# 110_ESP32s3.net
KiCad netlist of a schematic drawn in Altium Designer
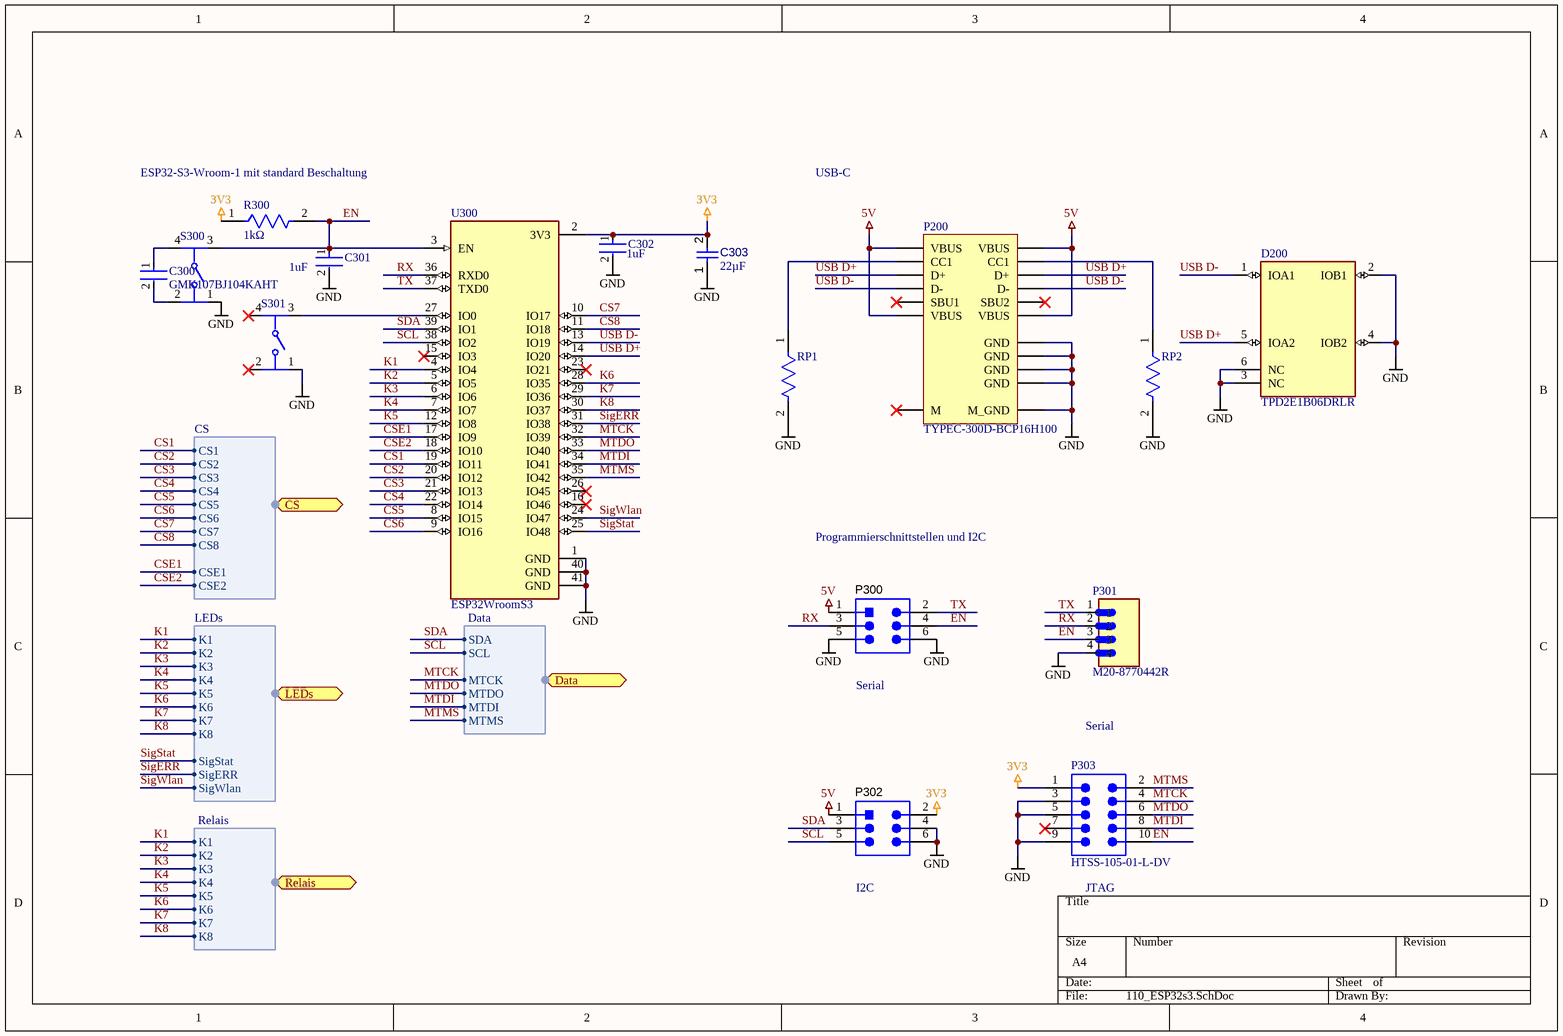
[diagram p0: 110_ESP32s3.SchDoc]

(export (version "E")
  (design (tool "Eeschema 10.0.6"))
  (components
    (comp (ref "C300")
      (value "GMK107BJ104KAHT")
      (footprint "FP-0603-L_1_6_0_1-W_0_8_0-IPC_B")
      (description "Ceramic Capacitor Automotive 0.1uF ±10% 35V X5R 0603")
      (fields (field (name "TOLERANCE") "10%"))
      (libsource (lib "Altium Content Vault") (part "02cd4be3c70576c341d710602a673aa"))
    )
    (comp (ref "C301")
      (value "1uF")
      (footprint "FP-CGA3E-0_3-0_1-MFG")
      (description "Cap Ceramic 1uF 35V X7R 10% Pad SMD 0603 +125°C Automotive T/R\r\nCGA3E1X7R1V105K080AC")
      (fields (field (name "TOLERANCE") "10%"))
      (libsource (lib "Altium Content Vault") (part "b4654b650e69147ec39a6b967a45e02"))
    )
    (comp (ref "C302")
      (value "1uF")
      (footprint "FP-CGA3E-0_3-0_1-MFG")
      (description "Cap Ceramic 1uF 35V X7R 10% Pad SMD 0603 +125°C Automotive T/R\r\nCGA3E1X7R1V105K080AC")
      (fields (field (name "TOLERANCE") "10%"))
      (libsource (lib "Altium Content Vault") (part "b4654b650e69147ec39a6b967a45e02"))
    )
    (comp (ref "C303")
      (value "22µF")
      (footprint "CAPC0805(2012)145_L")
      (description "Chip Capacitor, 22µF +/-40%, 16V, 0805, Thickness 1.45 mm")
      (fields (field (name "TOLERANCE") "5%") (field (name "Comment") "Capacitor 22µF +/-40% 16V 0805"))
      (libsource (lib "Milutin") (part "CAP-NP-2"))
    )
    (comp (ref "D200")
      (value "TPD2E1B06DRLR")
      (footprint "FP-DRL0006A-MFG")
      (description "TVS DIODE 5.5V 15V 6SOT")
      (fields
        (field (name "OCTOPART") "https://octopart.com/tpd2e1b06drlr-texas+instruments-30488860")
        (field (name "MANUFACTURER") "Texas Instruments")
      )
      (libsource (lib "Altium Content Vault") (part "f3dc085ebb28d99bc65c213f373c040"))
    )
    (comp (ref "P200")
      (value "TYPEC-300D-BCP16H100")
      (footprint "TYPEC-300D-BCP16H100-Footprint-1")
      (description "Vertical USB Type C Connector")
      (libsource (lib "Milutin") (part "TYPEC-300D-BCP16H100-Symbol-1"))
    )
    (comp (ref "P300")
      (value "5-146130-2")
      (footprint "TECO-5-146130-2_V")
      (description "Male Header, Pitch 2.54 mm, 2 x 3 Position, Height 8.13 mm, -65 to 125 degC, RoHS, Tube")
      (libsource (lib "Altium Content Vault") (part "CN-2P-M-R6"))
    )
    (comp (ref "P301")
      (value "M20-8770442R")
      (footprint "HARWIN_M20-8770442R")
      (description "Connector Header Surface Mount 4 position 0.100 (2.54mm)")
      (fields (field (name "MF") "Harwin Inc."))
      (libsource (lib "AltiumLib_MILUTIN") (part "M20-8770442R"))
    )
    (comp (ref "P302")
      (value "5-146130-2")
      (footprint "TECO-5-146130-2_V")
      (description "Male Header, Pitch 2.54 mm, 2 x 3 Position, Height 8.13 mm, -65 to 125 degC, RoHS, Tube")
      (libsource (lib "Altium Content Vault") (part "CN-2P-M-R6"))
    )
    (comp (ref "P303")
      (value "HTSS-105-01-L-DV")
      (footprint "SMTC-HTSS-105-01-X-DV")
      (fields (field (name "MANUFACTURER") "Samtec"))
      (libsource (lib "Altium Content Vault") (part "SMTC-HTSS-105-01-X-DV"))
    )
    (comp (ref "R300")
      (value "1kΩ")
      (footprint "FP-CRCW0603-e3-MFG")
      (description "RES Thick Film, 1kΩ, 1%, 0.1W, 100ppm/°C, 0603, CRCW06031K00FKEA")
      (fields (field (name "TOLERANCE") "1%"))
      (libsource (lib "Altium Content Vault") (part "1029c3af85768c4190bb7ad29bc67b5"))
    )
    (comp (ref "RP1")
      (value "CRCW06035K10FKEA")
      (footprint "FP-CRCW0603-e3-IPC_C")
      (description "RES Thick Film, 5.1kΩ, 1%, 0.1W, 100ppm/°C, 0603")
      (fields (field (name "TOLERANCE") "1%"))
      (libsource (lib "Altium Content Vault") (part "1029c3af85768c4190bb7ad29bc67b5"))
    )
    (comp (ref "RP2")
      (value "CRCW06035K10FKEA")
      (footprint "FP-CRCW0603-e3-IPC_C")
      (description "RES Thick Film, 5.1kΩ, 1%, 0.1W, 100ppm/°C, 0603")
      (fields (field (name "TOLERANCE") "1%"))
      (libsource (lib "Altium Content Vault") (part "1029c3af85768c4190bb7ad29bc67b5"))
    )
    (comp (ref "S300")
      (value "~")
      (footprint "FP-PTS645SM43SMTR92LFS-MFG")
      (description "SWITCH TACTILE SPST-NO 0.05A 12V\r\nPTS645SM43SMTR92LFS")
      (libsource (lib "Altium Content Vault") (part "1adf0dd01260c80cf25a44bfd6b99ba"))
    )
    (comp (ref "S301")
      (value "~")
      (footprint "FP-PTS645SM43SMTR92LFS-MFG")
      (description "SWITCH TACTILE SPST-NO 0.05A 12V\r\nPTS645SM43SMTR92LFS")
      (libsource (lib "Altium Content Vault") (part "1adf0dd01260c80cf25a44bfd6b99ba"))
    )
    (comp (ref "U300")
      (value "ESP32WroomS3")
      (footprint "ESP32WroomS3")
      (fields (field (name "SOURCE") "Schaltdose.SchLib"))
      (libsource (lib "Milutin") (part "ESP32WroomS3"))
    )
  )
  (nets
    (net (code "5") (name "/CS1") (class "Default")
      (node (ref "U300") (pin "19") (pinfunction "IO11_19") (pintype "bidirectional"))
    )
    (net (code "6") (name "/CS2") (class "Default")
      (node (ref "U300") (pin "20") (pinfunction "IO12_20") (pintype "bidirectional"))
    )
    (net (code "7") (name "/CS3") (class "Default")
      (node (ref "U300") (pin "21") (pinfunction "IO13_21") (pintype "bidirectional"))
    )
    (net (code "8") (name "/CS4") (class "Default")
      (node (ref "U300") (pin "22") (pinfunction "IO14_22") (pintype "bidirectional"))
    )
    (net (code "9") (name "/CS5") (class "Default")
      (node (ref "U300") (pin "8") (pinfunction "IO15_8") (pintype "bidirectional"))
    )
    (net (code "10") (name "/CS6") (class "Default")
      (node (ref "U300") (pin "9") (pinfunction "IO16_9") (pintype "bidirectional"))
    )
    (net (code "11") (name "/CS7") (class "Default")
      (node (ref "U300") (pin "10") (pinfunction "IO17_10") (pintype "bidirectional"))
    )
    (net (code "12") (name "/CS8") (class "Default")
      (node (ref "U300") (pin "11") (pinfunction "IO18_11") (pintype "bidirectional"))
    )
    (net (code "13") (name "/CSE1") (class "Default")
      (node (ref "U300") (pin "17") (pinfunction "IO9_17") (pintype "bidirectional"))
    )
    (net (code "14") (name "/CSE2") (class "Default")
      (node (ref "U300") (pin "18") (pinfunction "IO10_18") (pintype "bidirectional"))
    )
    (net (code "15") (name "/EN") (class "Default")
      (node (ref "C301") (pin "1") (pinfunction "1_1") (pintype "passive"))
      (node (ref "P300") (pin "4") (pinfunction "4_4") (pintype "passive"))
      (node (ref "P301") (pin "3") (pinfunction "3_3") (pintype "passive"))
      (node (ref "P303") (pin "10") (pinfunction "10_10") (pintype "passive"))
      (node (ref "R300") (pin "2") (pinfunction "2_2") (pintype "passive"))
      (node (ref "S300") (pin "3") (pinfunction "3_3") (pintype "passive"))
      (node (ref "U300") (pin "3") (pinfunction "EN_3") (pintype "input"))
    )
    (net (code "16") (name "/K1") (class "Default")
      (node (ref "U300") (pin "4") (pinfunction "IO4_4") (pintype "bidirectional"))
    )
    (net (code "17") (name "/K2") (class "Default")
      (node (ref "U300") (pin "5") (pinfunction "IO5_5") (pintype "bidirectional"))
    )
    (net (code "18") (name "/K3") (class "Default")
      (node (ref "U300") (pin "6") (pinfunction "IO6_6") (pintype "bidirectional"))
    )
    (net (code "19") (name "/K4") (class "Default")
      (node (ref "U300") (pin "7") (pinfunction "IO7_7") (pintype "bidirectional"))
    )
    (net (code "20") (name "/K5") (class "Default")
      (node (ref "U300") (pin "12") (pinfunction "IO8_12") (pintype "bidirectional"))
    )
    (net (code "21") (name "/K6") (class "Default")
      (node (ref "U300") (pin "28") (pinfunction "IO35_28") (pintype "bidirectional"))
    )
    (net (code "22") (name "/K7") (class "Default")
      (node (ref "U300") (pin "29") (pinfunction "IO36_29") (pintype "bidirectional"))
    )
    (net (code "23") (name "/K8") (class "Default")
      (node (ref "U300") (pin "30") (pinfunction "IO37_30") (pintype "bidirectional"))
    )
    (net (code "24") (name "/MTCK") (class "Default")
      (node (ref "P303") (pin "4") (pinfunction "4_4") (pintype "passive"))
      (node (ref "U300") (pin "32") (pinfunction "IO39_32") (pintype "bidirectional"))
    )
    (net (code "25") (name "/MTDI") (class "Default")
      (node (ref "P303") (pin "8") (pinfunction "8_8") (pintype "passive"))
      (node (ref "U300") (pin "34") (pinfunction "IO41_34") (pintype "bidirectional"))
    )
    (net (code "26") (name "/MTDO") (class "Default")
      (node (ref "P303") (pin "6") (pinfunction "6_6") (pintype "passive"))
      (node (ref "U300") (pin "33") (pinfunction "IO40_33") (pintype "bidirectional"))
    )
    (net (code "27") (name "/MTMS") (class "Default")
      (node (ref "P303") (pin "2") (pinfunction "2_2") (pintype "passive"))
      (node (ref "U300") (pin "35") (pinfunction "IO42_35") (pintype "bidirectional"))
    )
    (net (code "28") (name "/RX") (class "Default")
      (node (ref "P300") (pin "3") (pinfunction "3_3") (pintype "passive"))
      (node (ref "P301") (pin "2") (pinfunction "2_2") (pintype "passive"))
      (node (ref "U300") (pin "36") (pinfunction "RXD0_36") (pintype "bidirectional"))
    )
    (net (code "29") (name "/SCL") (class "Default")
      (node (ref "P302") (pin "5") (pinfunction "5_5") (pintype "passive"))
      (node (ref "U300") (pin "38") (pinfunction "IO2_38") (pintype "bidirectional"))
    )
    (net (code "30") (name "/SDA") (class "Default")
      (node (ref "P302") (pin "3") (pinfunction "3_3") (pintype "passive"))
      (node (ref "U300") (pin "39") (pinfunction "IO1_39") (pintype "bidirectional"))
    )
    (net (code "31") (name "/SigERR") (class "Default")
      (node (ref "U300") (pin "31") (pinfunction "IO38_31") (pintype "bidirectional"))
    )
    (net (code "32") (name "/SigStat") (class "Default")
      (node (ref "U300") (pin "25") (pinfunction "IO48_25") (pintype "bidirectional"))
    )
    (net (code "33") (name "/SigWlan") (class "Default")
      (node (ref "U300") (pin "24") (pinfunction "IO47_24") (pintype "bidirectional"))
    )
    (net (code "34") (name "/TX") (class "Default")
      (node (ref "P300") (pin "2") (pinfunction "2_2") (pintype "passive"))
      (node (ref "P301") (pin "1") (pinfunction "1_1") (pintype "passive"))
      (node (ref "U300") (pin "37") (pinfunction "TXD0_37") (pintype "bidirectional"))
    )
    (net (code "35") (name "/USB D+") (class "Default")
      (node (ref "D200") (pin "5") (pinfunction "IOA2_5") (pintype "bidirectional"))
      (node (ref "P200") (pin "A6") (pinfunction "D+_A6") (pintype "passive"))
      (node (ref "P200") (pin "B6") (pinfunction "D+_B6") (pintype "passive"))
      (node (ref "U300") (pin "14") (pinfunction "IO20_14") (pintype "bidirectional"))
    )
    (net (code "36") (name "/USB D-") (class "Default")
      (node (ref "D200") (pin "1") (pinfunction "IOA1_1") (pintype "bidirectional"))
      (node (ref "P200") (pin "A7") (pinfunction "D-_A7") (pintype "passive"))
      (node (ref "P200") (pin "B7") (pinfunction "D-_B7") (pintype "passive"))
      (node (ref "U300") (pin "13") (pinfunction "IO19_13") (pintype "bidirectional"))
    )
    (net (code "41") (name "3V3") (class "Default")
      (node (ref "C302") (pin "1") (pinfunction "1_1") (pintype "passive"))
      (node (ref "C303") (pin "2") (pinfunction "2_2") (pintype "passive"))
      (node (ref "P302") (pin "2") (pinfunction "2_2") (pintype "passive"))
      (node (ref "P303") (pin "1") (pinfunction "1_1") (pintype "passive"))
      (node (ref "R300") (pin "1") (pinfunction "1_1") (pintype "passive"))
      (node (ref "U300") (pin "2") (pinfunction "3V3_2") (pintype "power_in"))
    )
    (net (code "42") (name "5V") (class "Default")
      (node (ref "P200") (pin "A4") (pinfunction "VBUS_A4") (pintype "passive"))
      (node (ref "P200") (pin "A9") (pinfunction "VBUS_A9") (pintype "passive"))
      (node (ref "P200") (pin "B4") (pinfunction "VBUS_B4") (pintype "passive"))
      (node (ref "P200") (pin "B9") (pinfunction "VBUS_B9") (pintype "passive"))
      (node (ref "P300") (pin "1") (pinfunction "1_1") (pintype "passive"))
      (node (ref "P302") (pin "1") (pinfunction "1_1") (pintype "passive"))
    )
    (net (code "43") (name "GND") (class "Default")
      (node (ref "C301") (pin "2") (pinfunction "2_2") (pintype "passive"))
      (node (ref "C302") (pin "2") (pinfunction "2_2") (pintype "passive"))
      (node (ref "C303") (pin "1") (pinfunction "1_1") (pintype "passive"))
      (node (ref "D200") (pin "2") (pinfunction "IOB1_2") (pintype "bidirectional"))
      (node (ref "D200") (pin "3") (pinfunction "NC_3") (pintype "passive"))
      (node (ref "D200") (pin "4") (pinfunction "IOB2_4") (pintype "bidirectional"))
      (node (ref "D200") (pin "6") (pinfunction "NC_6") (pintype "passive"))
      (node (ref "P200") (pin "A1") (pinfunction "GND_A1") (pintype "passive"))
      (node (ref "P200") (pin "A12") (pinfunction "GND_A12") (pintype "passive"))
      (node (ref "P200") (pin "B1") (pinfunction "GND_B1") (pintype "passive"))
      (node (ref "P200") (pin "B12") (pinfunction "GND_B12") (pintype "passive"))
      (node (ref "P200") (pin "M_GND") (pinfunction "M_GND_M_GND") (pintype "passive"))
      (node (ref "P300") (pin "5") (pinfunction "5_5") (pintype "passive"))
      (node (ref "P300") (pin "6") (pinfunction "6_6") (pintype "passive"))
      (node (ref "P301") (pin "4") (pinfunction "4_4") (pintype "passive"))
      (node (ref "P302") (pin "4") (pinfunction "4_4") (pintype "passive"))
      (node (ref "P302") (pin "6") (pinfunction "6_6") (pintype "passive"))
      (node (ref "P303") (pin "3") (pinfunction "3_3") (pintype "passive"))
      (node (ref "P303") (pin "5") (pinfunction "5_5") (pintype "passive"))
      (node (ref "P303") (pin "9") (pinfunction "9_9") (pintype "passive"))
      (node (ref "RP1") (pin "2") (pinfunction "2_2") (pintype "passive"))
      (node (ref "RP2") (pin "2") (pinfunction "2_2") (pintype "passive"))
      (node (ref "S300") (pin "1") (pinfunction "1_1") (pintype "passive"))
      (node (ref "S301") (pin "1") (pinfunction "1_1") (pintype "passive"))
      (node (ref "U300") (pin "1") (pinfunction "GND_1") (pintype "power_in"))
      (node (ref "U300") (pin "40") (pinfunction "GND_40") (pintype "power_in"))
      (node (ref "U300") (pin "41") (pinfunction "GND_41") (pintype "power_in"))
    )
    (net (code "44") (name "Net-(C300-Pad1)") (class "Default")
      (node (ref "C300") (pin "1") (pinfunction "1_1") (pintype "passive"))
      (node (ref "S300") (pin "4") (pinfunction "4_4") (pintype "passive"))
    )
    (net (code "45") (name "Net-(C300-Pad2)") (class "Default")
      (node (ref "C300") (pin "2") (pinfunction "2_2") (pintype "passive"))
      (node (ref "S300") (pin "2") (pinfunction "2_2") (pintype "passive"))
    )
    (net (code "46") (name "Net-(P200-CC1-PadA5)") (class "Default")
      (node (ref "P200") (pin "A5") (pinfunction "CC1_A5") (pintype "passive"))
      (node (ref "RP1") (pin "1") (pinfunction "1_1") (pintype "passive"))
    )
    (net (code "47") (name "Net-(P200-CC1-PadB5)") (class "Default")
      (node (ref "P200") (pin "B5") (pinfunction "CC1_B5") (pintype "passive"))
      (node (ref "RP2") (pin "1") (pinfunction "1_1") (pintype "passive"))
    )
    (net (code "48") (name "Net-(U300-IO0)") (class "Default")
      (node (ref "S301") (pin "3") (pinfunction "3_3") (pintype "passive"))
      (node (ref "U300") (pin "27") (pinfunction "IO0_27") (pintype "bidirectional"))
    )
    (net (code "49") (name "unconnected-(P200-PadM)") (class "Default")
      (node (ref "P200") (pin "M") (pinfunction "M_M") (pintype "passive+no_connect"))
    )
    (net (code "50") (name "unconnected-(P200-SBU1-PadA8)") (class "Default")
      (node (ref "P200") (pin "A8") (pinfunction "SBU1_A8") (pintype "passive+no_connect"))
    )
    (net (code "51") (name "unconnected-(P200-SBU2-PadB8)") (class "Default")
      (node (ref "P200") (pin "B8") (pinfunction "SBU2_B8") (pintype "passive+no_connect"))
    )
    (net (code "52") (name "unconnected-(P303-Pad7)") (class "Default")
      (node (ref "P303") (pin "7") (pinfunction "7_7") (pintype "passive+no_connect"))
    )
    (net (code "53") (name "unconnected-(S301-Pad2)") (class "Default")
      (node (ref "S301") (pin "2") (pinfunction "2_2") (pintype "passive+no_connect"))
    )
    (net (code "54") (name "unconnected-(S301-Pad4)") (class "Default")
      (node (ref "S301") (pin "4") (pinfunction "4_4") (pintype "passive+no_connect"))
    )
    (net (code "55") (name "unconnected-(U300-IO3-Pad15)") (class "Default")
      (node (ref "U300") (pin "15") (pinfunction "IO3_15") (pintype "bidirectional+no_connect"))
    )
    (net (code "56") (name "unconnected-(U300-IO21-Pad23)") (class "Default")
      (node (ref "U300") (pin "23") (pinfunction "IO21_23") (pintype "bidirectional+no_connect"))
    )
    (net (code "57") (name "unconnected-(U300-IO45-Pad26)") (class "Default")
      (node (ref "U300") (pin "26") (pinfunction "IO45_26") (pintype "bidirectional+no_connect"))
    )
    (net (code "58") (name "unconnected-(U300-IO46-Pad16)") (class "Default")
      (node (ref "U300") (pin "16") (pinfunction "IO46_16") (pintype "bidirectional+no_connect"))
    )
  )
)
